# M3_Chip.net
KiCad netlist of a schematic drawn in Altium Designer
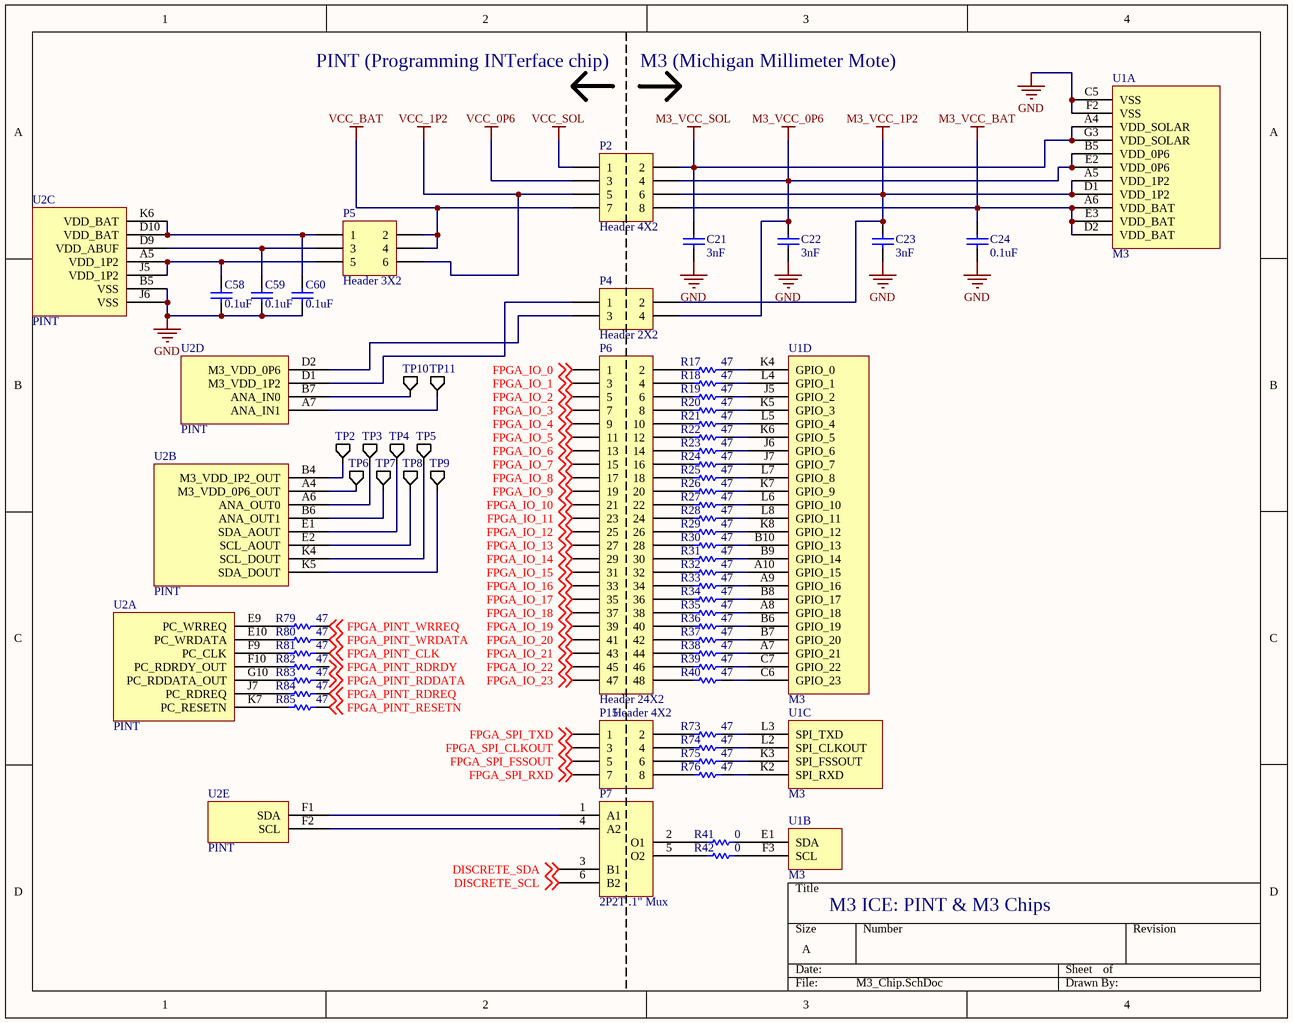
[diagram p0: M3_Chip.SchDoc]

(export (version "E")
  (design (tool "Eeschema 10.0.6"))
  (components
    (comp (ref "C21")
      (value "3nF")
      (footprint "1608[0603]")
      (description "Capacitor (Semiconductor SIM Model)")
      (fields
        (field (name "DISTPARTNO") "399-7893-1-ND")
        (field (name "MANPARTNO") "C0603C302K5GACTU")
        (field (name "PUBLISHER") "Altium Limited")
      )
      (libsource (lib "Miscellaneous Devices") (part "Cap Semi"))
    )
    (comp (ref "C22")
      (value "3nF")
      (footprint "1608[0603]")
      (description "Capacitor (Semiconductor SIM Model)")
      (fields
        (field (name "DISTPARTNO") "399-7893-1-ND")
        (field (name "MANPARTNO") "C0603C302K5GACTU")
        (field (name "PUBLISHER") "Altium Limited")
      )
      (libsource (lib "Miscellaneous Devices") (part "Cap Semi"))
    )
    (comp (ref "C23")
      (value "3nF")
      (footprint "1608[0603]")
      (description "Capacitor (Semiconductor SIM Model)")
      (fields
        (field (name "DISTPARTNO") "399-7893-1-ND")
        (field (name "MANPARTNO") "C0603C302K5GACTU")
        (field (name "PUBLISHER") "Altium Limited")
      )
      (libsource (lib "Miscellaneous Devices") (part "Cap Semi"))
    )
    (comp (ref "C24")
      (value "0.1uF")
      (footprint "1608[0603]")
      (description "Capacitor (Semiconductor SIM Model)")
      (fields
        (field (name "DISTPARTNO") "445-1317-1-ND")
        (field (name "MANPARTNO") "C1608X7R1C104K")
        (field (name "PUBLISHER") "Altium Limited")
      )
      (libsource (lib "Miscellaneous Devices") (part "Cap Semi"))
    )
    (comp (ref "C58")
      (value "0.1uF")
      (footprint "1608[0603]")
      (description "Capacitor (Semiconductor SIM Model)")
      (fields
        (field (name "DISTPARTNO") "445-1317-1-ND")
        (field (name "MANPARTNO") "C1608X7R1C104K")
        (field (name "PUBLISHER") "Altium Limited")
      )
      (libsource (lib "Miscellaneous Devices") (part "Cap Semi"))
    )
    (comp (ref "C59")
      (value "0.1uF")
      (footprint "1608[0603]")
      (description "Capacitor (Semiconductor SIM Model)")
      (fields
        (field (name "DISTPARTNO") "445-1317-1-ND")
        (field (name "MANPARTNO") "C1608X7R1C104K")
        (field (name "PUBLISHER") "Altium Limited")
      )
      (libsource (lib "Miscellaneous Devices") (part "Cap Semi"))
    )
    (comp (ref "C60")
      (value "0.1uF")
      (footprint "1608[0603]")
      (description "Capacitor (Semiconductor SIM Model)")
      (fields
        (field (name "DISTPARTNO") "445-1317-1-ND")
        (field (name "MANPARTNO") "C1608X7R1C104K")
        (field (name "PUBLISHER") "Altium Limited")
      )
      (libsource (lib "Miscellaneous Devices") (part "Cap Semi"))
    )
    (comp (ref "P2")
      (value "Header 4X2")
      (footprint "HDR2X4")
      (description "Header, 4-Pin, Dual row")
      (fields (field (name "PUBLISHER") "Altium Limited"))
      (libsource (lib "Miscellaneous Connectors") (part "Header 4X2"))
    )
    (comp (ref "P4")
      (value "Header 2X2")
      (footprint "HDR2X2")
      (description "Header, 2-Pin, Dual row")
      (fields (field (name "PUBLISHER") "Altium Limited"))
      (libsource (lib "Miscellaneous Connectors") (part "Header 2X2"))
    )
    (comp (ref "P5")
      (value "Header 3X2")
      (footprint "HDR2X3")
      (description "Header, 3-Pin, Dual row")
      (fields (field (name "PUBLISHER") "Altium Limited"))
      (libsource (lib "Miscellaneous Connectors") (part "Header 3X2"))
    )
    (comp (ref "P6")
      (value "Header 24X2")
      (footprint "HDR2X24")
      (description "Header, 24-Pin, Dual row")
      (fields (field (name "PUBLISHER") "Altium Limited"))
      (libsource (lib "Miscellaneous Connectors") (part "Header 24X2"))
    )
    (comp (ref "P7")
      (value "2P2T .1\" Mux")
      (footprint "HDR3x2")
      (libsource (lib "M3") (part "2P2T .1{dblquote} Mux"))
    )
    (comp (ref "P15")
      (value "Header 4X2")
      (footprint "HDR2X4")
      (description "Header, 4-Pin, Dual row")
      (fields (field (name "PUBLISHER") "Altium Limited"))
      (libsource (lib "Miscellaneous Connectors") (part "Header 4X2"))
    )
    (comp (ref "R17")
      (value "47")
      (footprint "0603")
      (description "Semiconductor Resistor")
      (fields
        (field (name "DISTPARTNO") "P47GCT-ND")
        (field (name "MANPARTNO") "ERJ-3GEYJ470V")
        (field (name "PUBLISHER") "Altium Limited")
      )
      (libsource (lib "M3") (part "Res Chip"))
    )
    (comp (ref "R18")
      (value "47")
      (footprint "0603")
      (description "Semiconductor Resistor")
      (fields
        (field (name "DISTPARTNO") "P47GCT-ND")
        (field (name "MANPARTNO") "ERJ-3GEYJ470V")
        (field (name "PUBLISHER") "Altium Limited")
      )
      (libsource (lib "M3") (part "Res Chip"))
    )
    (comp (ref "R19")
      (value "47")
      (footprint "0603")
      (description "Semiconductor Resistor")
      (fields
        (field (name "DISTPARTNO") "P47GCT-ND")
        (field (name "MANPARTNO") "ERJ-3GEYJ470V")
        (field (name "PUBLISHER") "Altium Limited")
      )
      (libsource (lib "M3") (part "Res Chip"))
    )
    (comp (ref "R20")
      (value "47")
      (footprint "0603")
      (description "Semiconductor Resistor")
      (fields
        (field (name "DISTPARTNO") "P47GCT-ND")
        (field (name "MANPARTNO") "ERJ-3GEYJ470V")
        (field (name "PUBLISHER") "Altium Limited")
      )
      (libsource (lib "M3") (part "Res Chip"))
    )
    (comp (ref "R21")
      (value "47")
      (footprint "0603")
      (description "Semiconductor Resistor")
      (fields
        (field (name "DISTPARTNO") "P47GCT-ND")
        (field (name "MANPARTNO") "ERJ-3GEYJ470V")
        (field (name "PUBLISHER") "Altium Limited")
      )
      (libsource (lib "M3") (part "Res Chip"))
    )
    (comp (ref "R22")
      (value "47")
      (footprint "0603")
      (description "Semiconductor Resistor")
      (fields
        (field (name "DISTPARTNO") "P47GCT-ND")
        (field (name "MANPARTNO") "ERJ-3GEYJ470V")
        (field (name "PUBLISHER") "Altium Limited")
      )
      (libsource (lib "M3") (part "Res Chip"))
    )
    (comp (ref "R23")
      (value "47")
      (footprint "0603")
      (description "Semiconductor Resistor")
      (fields
        (field (name "DISTPARTNO") "P47GCT-ND")
        (field (name "MANPARTNO") "ERJ-3GEYJ470V")
        (field (name "PUBLISHER") "Altium Limited")
      )
      (libsource (lib "M3") (part "Res Chip"))
    )
    (comp (ref "R24")
      (value "47")
      (footprint "0603")
      (description "Semiconductor Resistor")
      (fields
        (field (name "DISTPARTNO") "P47GCT-ND")
        (field (name "MANPARTNO") "ERJ-3GEYJ470V")
        (field (name "PUBLISHER") "Altium Limited")
      )
      (libsource (lib "M3") (part "Res Chip"))
    )
    (comp (ref "R25")
      (value "47")
      (footprint "0603")
      (description "Semiconductor Resistor")
      (fields
        (field (name "DISTPARTNO") "P47GCT-ND")
        (field (name "MANPARTNO") "ERJ-3GEYJ470V")
        (field (name "PUBLISHER") "Altium Limited")
      )
      (libsource (lib "M3") (part "Res Chip"))
    )
    (comp (ref "R26")
      (value "47")
      (footprint "0603")
      (description "Semiconductor Resistor")
      (fields
        (field (name "DISTPARTNO") "P47GCT-ND")
        (field (name "MANPARTNO") "ERJ-3GEYJ470V")
        (field (name "PUBLISHER") "Altium Limited")
      )
      (libsource (lib "M3") (part "Res Chip"))
    )
    (comp (ref "R27")
      (value "47")
      (footprint "0603")
      (description "Semiconductor Resistor")
      (fields
        (field (name "DISTPARTNO") "P47GCT-ND")
        (field (name "MANPARTNO") "ERJ-3GEYJ470V")
        (field (name "PUBLISHER") "Altium Limited")
      )
      (libsource (lib "M3") (part "Res Chip"))
    )
    (comp (ref "R28")
      (value "47")
      (footprint "0603")
      (description "Semiconductor Resistor")
      (fields
        (field (name "DISTPARTNO") "P47GCT-ND")
        (field (name "MANPARTNO") "ERJ-3GEYJ470V")
        (field (name "PUBLISHER") "Altium Limited")
      )
      (libsource (lib "M3") (part "Res Chip"))
    )
    (comp (ref "R29")
      (value "47")
      (footprint "0603")
      (description "Semiconductor Resistor")
      (fields
        (field (name "DISTPARTNO") "P47GCT-ND")
        (field (name "MANPARTNO") "ERJ-3GEYJ470V")
        (field (name "PUBLISHER") "Altium Limited")
      )
      (libsource (lib "M3") (part "Res Chip"))
    )
    (comp (ref "R30")
      (value "47")
      (footprint "0603")
      (description "Semiconductor Resistor")
      (fields
        (field (name "DISTPARTNO") "P47GCT-ND")
        (field (name "MANPARTNO") "ERJ-3GEYJ470V")
        (field (name "PUBLISHER") "Altium Limited")
      )
      (libsource (lib "M3") (part "Res Chip"))
    )
    (comp (ref "R31")
      (value "47")
      (footprint "0603")
      (description "Semiconductor Resistor")
      (fields
        (field (name "DISTPARTNO") "P47GCT-ND")
        (field (name "MANPARTNO") "ERJ-3GEYJ470V")
        (field (name "PUBLISHER") "Altium Limited")
      )
      (libsource (lib "M3") (part "Res Chip"))
    )
    (comp (ref "R32")
      (value "47")
      (footprint "0603")
      (description "Semiconductor Resistor")
      (fields
        (field (name "DISTPARTNO") "P47GCT-ND")
        (field (name "MANPARTNO") "ERJ-3GEYJ470V")
        (field (name "PUBLISHER") "Altium Limited")
      )
      (libsource (lib "M3") (part "Res Chip"))
    )
    (comp (ref "R33")
      (value "47")
      (footprint "0603")
      (description "Semiconductor Resistor")
      (fields
        (field (name "DISTPARTNO") "P47GCT-ND")
        (field (name "MANPARTNO") "ERJ-3GEYJ470V")
        (field (name "PUBLISHER") "Altium Limited")
      )
      (libsource (lib "M3") (part "Res Chip"))
    )
    (comp (ref "R34")
      (value "47")
      (footprint "0603")
      (description "Semiconductor Resistor")
      (fields
        (field (name "DISTPARTNO") "P47GCT-ND")
        (field (name "MANPARTNO") "ERJ-3GEYJ470V")
        (field (name "PUBLISHER") "Altium Limited")
      )
      (libsource (lib "M3") (part "Res Chip"))
    )
    (comp (ref "R35")
      (value "47")
      (footprint "0603")
      (description "Semiconductor Resistor")
      (fields
        (field (name "DISTPARTNO") "P47GCT-ND")
        (field (name "MANPARTNO") "ERJ-3GEYJ470V")
        (field (name "PUBLISHER") "Altium Limited")
      )
      (libsource (lib "M3") (part "Res Chip"))
    )
    (comp (ref "R36")
      (value "47")
      (footprint "0603")
      (description "Semiconductor Resistor")
      (fields
        (field (name "DISTPARTNO") "P47GCT-ND")
        (field (name "MANPARTNO") "ERJ-3GEYJ470V")
        (field (name "PUBLISHER") "Altium Limited")
      )
      (libsource (lib "M3") (part "Res Chip"))
    )
    (comp (ref "R37")
      (value "47")
      (footprint "0603")
      (description "Semiconductor Resistor")
      (fields
        (field (name "DISTPARTNO") "P47GCT-ND")
        (field (name "MANPARTNO") "ERJ-3GEYJ470V")
        (field (name "PUBLISHER") "Altium Limited")
      )
      (libsource (lib "M3") (part "Res Chip"))
    )
    (comp (ref "R38")
      (value "47")
      (footprint "0603")
      (description "Semiconductor Resistor")
      (fields
        (field (name "DISTPARTNO") "P47GCT-ND")
        (field (name "MANPARTNO") "ERJ-3GEYJ470V")
        (field (name "PUBLISHER") "Altium Limited")
      )
      (libsource (lib "M3") (part "Res Chip"))
    )
    (comp (ref "R39")
      (value "47")
      (footprint "0603")
      (description "Semiconductor Resistor")
      (fields
        (field (name "DISTPARTNO") "P47GCT-ND")
        (field (name "MANPARTNO") "ERJ-3GEYJ470V")
        (field (name "PUBLISHER") "Altium Limited")
      )
      (libsource (lib "M3") (part "Res Chip"))
    )
    (comp (ref "R40")
      (value "47")
      (footprint "0603")
      (description "Semiconductor Resistor")
      (fields
        (field (name "DISTPARTNO") "P47GCT-ND")
        (field (name "MANPARTNO") "ERJ-3GEYJ470V")
        (field (name "PUBLISHER") "Altium Limited")
      )
      (libsource (lib "M3") (part "Res Chip"))
    )
    (comp (ref "R41")
      (value "0")
      (footprint "0603")
      (description "Semiconductor Resistor")
      (fields
        (field (name "DISTPARTNO") "P0.0GCT-ND")
        (field (name "MANPARTNO") "ERJ-3GEY0R00V")
        (field (name "PUBLISHER") "Altium Limited")
      )
      (libsource (lib "M3") (part "Res Chip"))
    )
    (comp (ref "R42")
      (value "0")
      (footprint "0603")
      (description "Semiconductor Resistor")
      (fields
        (field (name "DISTPARTNO") "P0.0GCT-ND")
        (field (name "MANPARTNO") "ERJ-3GEY0R00V")
        (field (name "PUBLISHER") "Altium Limited")
      )
      (libsource (lib "M3") (part "Res Chip"))
    )
    (comp (ref "R73")
      (value "47")
      (footprint "0603")
      (description "Semiconductor Resistor")
      (fields
        (field (name "DISTPARTNO") "P47GCT-ND")
        (field (name "MANPARTNO") "ERJ-3GEYJ470V")
        (field (name "PUBLISHER") "Altium Limited")
      )
      (libsource (lib "M3") (part "Res Chip"))
    )
    (comp (ref "R74")
      (value "47")
      (footprint "0603")
      (description "Semiconductor Resistor")
      (fields
        (field (name "DISTPARTNO") "P47GCT-ND")
        (field (name "MANPARTNO") "ERJ-3GEYJ470V")
        (field (name "PUBLISHER") "Altium Limited")
      )
      (libsource (lib "M3") (part "Res Chip"))
    )
    (comp (ref "R75")
      (value "47")
      (footprint "0603")
      (description "Semiconductor Resistor")
      (fields
        (field (name "DISTPARTNO") "P47GCT-ND")
        (field (name "MANPARTNO") "ERJ-3GEYJ470V")
        (field (name "PUBLISHER") "Altium Limited")
      )
      (libsource (lib "M3") (part "Res Chip"))
    )
    (comp (ref "R76")
      (value "47")
      (footprint "0603")
      (description "Semiconductor Resistor")
      (fields
        (field (name "DISTPARTNO") "P47GCT-ND")
        (field (name "MANPARTNO") "ERJ-3GEYJ470V")
        (field (name "PUBLISHER") "Altium Limited")
      )
      (libsource (lib "M3") (part "Res Chip"))
    )
    (comp (ref "R79")
      (value "47")
      (footprint "0603")
      (description "Semiconductor Resistor")
      (fields
        (field (name "DISTPARTNO") "P47GCT-ND")
        (field (name "MANPARTNO") "ERJ-3GEYJ470V")
        (field (name "PUBLISHER") "Altium Limited")
      )
      (libsource (lib "M3") (part "Res Chip"))
    )
    (comp (ref "R80")
      (value "47")
      (footprint "0603")
      (description "Semiconductor Resistor")
      (fields
        (field (name "DISTPARTNO") "P47GCT-ND")
        (field (name "MANPARTNO") "ERJ-3GEYJ470V")
        (field (name "PUBLISHER") "Altium Limited")
      )
      (libsource (lib "M3") (part "Res Chip"))
    )
    (comp (ref "R81")
      (value "47")
      (footprint "0603")
      (description "Semiconductor Resistor")
      (fields
        (field (name "DISTPARTNO") "P47GCT-ND")
        (field (name "MANPARTNO") "ERJ-3GEYJ470V")
        (field (name "PUBLISHER") "Altium Limited")
      )
      (libsource (lib "M3") (part "Res Chip"))
    )
    (comp (ref "R82")
      (value "47")
      (footprint "0603")
      (description "Semiconductor Resistor")
      (fields
        (field (name "DISTPARTNO") "P47GCT-ND")
        (field (name "MANPARTNO") "ERJ-3GEYJ470V")
        (field (name "PUBLISHER") "Altium Limited")
      )
      (libsource (lib "M3") (part "Res Chip"))
    )
    (comp (ref "R83")
      (value "47")
      (footprint "0603")
      (description "Semiconductor Resistor")
      (fields
        (field (name "DISTPARTNO") "P47GCT-ND")
        (field (name "MANPARTNO") "ERJ-3GEYJ470V")
        (field (name "PUBLISHER") "Altium Limited")
      )
      (libsource (lib "M3") (part "Res Chip"))
    )
    (comp (ref "R84")
      (value "47")
      (footprint "0603")
      (description "Semiconductor Resistor")
      (fields
        (field (name "DISTPARTNO") "P47GCT-ND")
        (field (name "MANPARTNO") "ERJ-3GEYJ470V")
        (field (name "PUBLISHER") "Altium Limited")
      )
      (libsource (lib "M3") (part "Res Chip"))
    )
    (comp (ref "R85")
      (value "47")
      (footprint "0603")
      (description "Semiconductor Resistor")
      (fields
        (field (name "DISTPARTNO") "P47GCT-ND")
        (field (name "MANPARTNO") "ERJ-3GEYJ470V")
        (field (name "PUBLISHER") "Altium Limited")
      )
      (libsource (lib "M3") (part "Res Chip"))
    )
    (comp (ref "TP2") (value "TP") (footprint "TP") (libsource (lib "M3") (part "TP")))
    (comp (ref "TP3") (value "TP") (footprint "TP") (libsource (lib "M3") (part "TP")))
    (comp (ref "TP4") (value "TP") (footprint "TP") (libsource (lib "M3") (part "TP")))
    (comp (ref "TP5") (value "TP") (footprint "TP") (libsource (lib "M3") (part "TP")))
    (comp (ref "TP6") (value "TP") (footprint "TP") (libsource (lib "M3") (part "TP")))
    (comp (ref "TP7") (value "TP") (footprint "TP") (libsource (lib "M3") (part "TP")))
    (comp (ref "TP8") (value "TP") (footprint "TP") (libsource (lib "M3") (part "TP")))
    (comp (ref "TP9") (value "TP") (footprint "TP") (libsource (lib "M3") (part "TP")))
    (comp (ref "TP10") (value "TP") (footprint "TP") (libsource (lib "M3") (part "TP")))
    (comp (ref "TP11") (value "TP") (footprint "TP") (libsource (lib "M3") (part "TP")))
    (comp (ref "U1")
      (value "M3")
      (footprint "CPGA-84")
      (fields (field (name "DISTPARTNO") "3M5067-ND") (field (name "MANPARTNO") "200-6311-9UN-1900"))
      (libsource (lib "M3") (part "M3"))
    )
    (comp (ref "U2")
      (value "PINT")
      (footprint "CPGA-65")
      (fields (field (name "DISTPARTNO") "3M5066-ND") (field (name "MANPARTNO") "200-6310-9UN-1900"))
      (libsource (lib "M3") (part "PINT"))
    )
  )
  (nets
    (net (code "1") (name "DISCRETE_SCL") (class "Default")
      (node (ref "P7") (pin "6") (pinfunction "B2_6") (pintype "passive"))
    )
    (net (code "2") (name "DISCRETE_SDA") (class "Default")
      (node (ref "P7") (pin "3") (pinfunction "B1_3") (pintype "passive"))
    )
    (net (code "3") (name "FPGA_IO_0") (class "Default")
      (node (ref "P6") (pin "1") (pinfunction "1_1") (pintype "passive"))
    )
    (net (code "4") (name "FPGA_IO_1") (class "Default")
      (node (ref "P6") (pin "3") (pinfunction "3_3") (pintype "passive"))
    )
    (net (code "5") (name "FPGA_IO_2") (class "Default")
      (node (ref "P6") (pin "5") (pinfunction "5_5") (pintype "passive"))
    )
    (net (code "6") (name "FPGA_IO_3") (class "Default")
      (node (ref "P6") (pin "7") (pinfunction "7_7") (pintype "passive"))
    )
    (net (code "7") (name "FPGA_IO_4") (class "Default")
      (node (ref "P6") (pin "9") (pinfunction "9_9") (pintype "passive"))
    )
    (net (code "8") (name "FPGA_IO_5") (class "Default")
      (node (ref "P6") (pin "11") (pinfunction "11_11") (pintype "passive"))
    )
    (net (code "9") (name "FPGA_IO_6") (class "Default")
      (node (ref "P6") (pin "13") (pinfunction "13_13") (pintype "passive"))
    )
    (net (code "10") (name "FPGA_IO_7") (class "Default")
      (node (ref "P6") (pin "15") (pinfunction "15_15") (pintype "passive"))
    )
    (net (code "11") (name "FPGA_IO_8") (class "Default")
      (node (ref "P6") (pin "17") (pinfunction "17_17") (pintype "passive"))
    )
    (net (code "12") (name "FPGA_IO_9") (class "Default")
      (node (ref "P6") (pin "19") (pinfunction "19_19") (pintype "passive"))
    )
    (net (code "13") (name "FPGA_IO_10") (class "Default")
      (node (ref "P6") (pin "21") (pinfunction "21_21") (pintype "passive"))
    )
    (net (code "14") (name "FPGA_IO_11") (class "Default")
      (node (ref "P6") (pin "23") (pinfunction "23_23") (pintype "passive"))
    )
    (net (code "15") (name "FPGA_IO_12") (class "Default")
      (node (ref "P6") (pin "25") (pinfunction "25_25") (pintype "passive"))
    )
    (net (code "16") (name "FPGA_IO_13") (class "Default")
      (node (ref "P6") (pin "27") (pinfunction "27_27") (pintype "passive"))
    )
    (net (code "17") (name "FPGA_IO_14") (class "Default")
      (node (ref "P6") (pin "29") (pinfunction "29_29") (pintype "passive"))
    )
    (net (code "18") (name "FPGA_IO_15") (class "Default")
      (node (ref "P6") (pin "31") (pinfunction "31_31") (pintype "passive"))
    )
    (net (code "19") (name "FPGA_IO_16") (class "Default")
      (node (ref "P6") (pin "33") (pinfunction "33_33") (pintype "passive"))
    )
    (net (code "20") (name "FPGA_IO_17") (class "Default")
      (node (ref "P6") (pin "35") (pinfunction "35_35") (pintype "passive"))
    )
    (net (code "21") (name "FPGA_IO_18") (class "Default")
      (node (ref "P6") (pin "37") (pinfunction "37_37") (pintype "passive"))
    )
    (net (code "22") (name "FPGA_IO_19") (class "Default")
      (node (ref "P6") (pin "39") (pinfunction "39_39") (pintype "passive"))
    )
    (net (code "23") (name "FPGA_IO_20") (class "Default")
      (node (ref "P6") (pin "41") (pinfunction "41_41") (pintype "passive"))
    )
    (net (code "24") (name "FPGA_IO_21") (class "Default")
      (node (ref "P6") (pin "43") (pinfunction "43_43") (pintype "passive"))
    )
    (net (code "25") (name "FPGA_IO_22") (class "Default")
      (node (ref "P6") (pin "45") (pinfunction "45_45") (pintype "passive"))
    )
    (net (code "26") (name "FPGA_IO_23") (class "Default")
      (node (ref "P6") (pin "47") (pinfunction "47_47") (pintype "passive"))
    )
    (net (code "27") (name "FPGA_PINT_CLK") (class "Default")
      (node (ref "R81") (pin "1") (pinfunction "1_1") (pintype "passive"))
    )
    (net (code "28") (name "FPGA_PINT_RDDATA") (class "Default")
      (node (ref "R83") (pin "1") (pinfunction "1_1") (pintype "passive"))
    )
    (net (code "29") (name "FPGA_PINT_RDRDY") (class "Default")
      (node (ref "R82") (pin "1") (pinfunction "1_1") (pintype "passive"))
    )
    (net (code "30") (name "FPGA_PINT_RDREQ") (class "Default")
      (node (ref "R84") (pin "1") (pinfunction "1_1") (pintype "passive"))
    )
    (net (code "31") (name "FPGA_PINT_RESETN") (class "Default")
      (node (ref "R85") (pin "1") (pinfunction "1_1") (pintype "passive"))
    )
    (net (code "32") (name "FPGA_PINT_WRDATA") (class "Default")
      (node (ref "R80") (pin "1") (pinfunction "1_1") (pintype "passive"))
    )
    (net (code "33") (name "FPGA_PINT_WRREQ") (class "Default")
      (node (ref "R79") (pin "1") (pinfunction "1_1") (pintype "passive"))
    )
    (net (code "34") (name "FPGA_SPI_CLKOUT") (class "Default")
      (node (ref "P15") (pin "3") (pinfunction "3_3") (pintype "passive"))
    )
    (net (code "35") (name "FPGA_SPI_FSSOUT") (class "Default")
      (node (ref "P15") (pin "5") (pinfunction "5_5") (pintype "passive"))
    )
    (net (code "36") (name "FPGA_SPI_RXD") (class "Default")
      (node (ref "P15") (pin "7") (pinfunction "7_7") (pintype "passive"))
    )
    (net (code "37") (name "FPGA_SPI_TXD") (class "Default")
      (node (ref "P15") (pin "1") (pinfunction "1_1") (pintype "passive"))
    )
    (net (code "38") (name "GND") (class "Default")
      (node (ref "C21") (pin "1") (pinfunction "1_1") (pintype "passive"))
      (node (ref "C22") (pin "1") (pinfunction "1_1") (pintype "passive"))
      (node (ref "C23") (pin "1") (pinfunction "1_1") (pintype "passive"))
      (node (ref "C24") (pin "1") (pinfunction "1_1") (pintype "passive"))
      (node (ref "C58") (pin "1") (pinfunction "1_1") (pintype "passive"))
      (node (ref "C59") (pin "1") (pinfunction "1_1") (pintype "passive"))
      (node (ref "C60") (pin "1") (pinfunction "1_1") (pintype "passive"))
      (node (ref "U1") (pin "C5") (pinfunction "VSS_C5") (pintype "passive"))
      (node (ref "U1") (pin "F2") (pinfunction "VSS_F2") (pintype "passive"))
      (node (ref "U2") (pin "B5") (pinfunction "VSS_B5") (pintype "passive"))
      (node (ref "U2") (pin "J6") (pinfunction "VSS_J6") (pintype "passive"))
    )
    (net (code "39") (name "M3_VCC_0P6") (class "Default")
      (node (ref "C22") (pin "2") (pinfunction "2_2") (pintype "passive"))
      (node (ref "P2") (pin "4") (pinfunction "4_4") (pintype "passive"))
      (node (ref "P4") (pin "4") (pinfunction "4_4") (pintype "passive"))
      (node (ref "U1") (pin "B5") (pinfunction "VDD_0P6_B5") (pintype "passive"))
      (node (ref "U1") (pin "E2") (pinfunction "VDD_0P6_E2") (pintype "passive"))
    )
    (net (code "40") (name "M3_VCC_1P2") (class "Default")
      (node (ref "C23") (pin "2") (pinfunction "2_2") (pintype "passive"))
      (node (ref "P2") (pin "6") (pinfunction "6_6") (pintype "passive"))
      (node (ref "P4") (pin "2") (pinfunction "2_2") (pintype "passive"))
      (node (ref "U1") (pin "A5") (pinfunction "VDD_1P2_A5") (pintype "passive"))
      (node (ref "U1") (pin "D1") (pinfunction "VDD_1P2_D1") (pintype "passive"))
    )
    (net (code "41") (name "M3_VCC_BAT") (class "Default")
      (node (ref "C24") (pin "2") (pinfunction "2_2") (pintype "passive"))
      (node (ref "P2") (pin "8") (pinfunction "8_8") (pintype "passive"))
      (node (ref "U1") (pin "A6") (pinfunction "VDD_BAT_A6") (pintype "passive"))
      (node (ref "U1") (pin "D2") (pinfunction "VDD_BAT_D2") (pintype "passive"))
      (node (ref "U1") (pin "E3") (pinfunction "VDD_BAT_E3") (pintype "passive"))
    )
    (net (code "42") (name "M3_VCC_SOL") (class "Default")
      (node (ref "C21") (pin "2") (pinfunction "2_2") (pintype "passive"))
      (node (ref "P2") (pin "2") (pinfunction "2_2") (pintype "passive"))
      (node (ref "U1") (pin "A4") (pinfunction "VDD_SOLAR_A4") (pintype "passive"))
      (node (ref "U1") (pin "G3") (pinfunction "VDD_SOLAR_G3") (pintype "passive"))
    )
    (net (code "43") (name "Net-(C58-Pad2)") (class "Default")
      (node (ref "C58") (pin "2") (pinfunction "2_2") (pintype "passive"))
      (node (ref "P5") (pin "5") (pinfunction "5_5") (pintype "passive"))
      (node (ref "U2") (pin "A5") (pinfunction "VDD_1P2_A5") (pintype "passive"))
      (node (ref "U2") (pin "J5") (pinfunction "VDD_1P2_J5") (pintype "passive"))
    )
    (net (code "44") (name "Net-(C60-Pad2)") (class "Default")
      (node (ref "C60") (pin "2") (pinfunction "2_2") (pintype "passive"))
      (node (ref "P5") (pin "1") (pinfunction "1_1") (pintype "passive"))
      (node (ref "U2") (pin "D10") (pinfunction "VDD_BAT_D10") (pintype "passive"))
      (node (ref "U2") (pin "K6") (pinfunction "VDD_BAT_K6") (pintype "passive"))
    )
    (net (code "45") (name "Net-(P6-Pad2)") (class "Default")
      (node (ref "P6") (pin "2") (pinfunction "2_2") (pintype "passive"))
      (node (ref "R17") (pin "2") (pinfunction "2_2") (pintype "passive"))
    )
    (net (code "46") (name "Net-(P6-Pad4)") (class "Default")
      (node (ref "P6") (pin "4") (pinfunction "4_4") (pintype "passive"))
      (node (ref "R18") (pin "2") (pinfunction "2_2") (pintype "passive"))
    )
    (net (code "47") (name "Net-(P6-Pad6)") (class "Default")
      (node (ref "P6") (pin "6") (pinfunction "6_6") (pintype "passive"))
      (node (ref "R19") (pin "2") (pinfunction "2_2") (pintype "passive"))
    )
    (net (code "48") (name "Net-(P6-Pad8)") (class "Default")
      (node (ref "P6") (pin "8") (pinfunction "8_8") (pintype "passive"))
      (node (ref "R20") (pin "2") (pinfunction "2_2") (pintype "passive"))
    )
    (net (code "49") (name "Net-(P6-Pad10)") (class "Default")
      (node (ref "P6") (pin "10") (pinfunction "10_10") (pintype "passive"))
      (node (ref "R21") (pin "2") (pinfunction "2_2") (pintype "passive"))
    )
    (net (code "50") (name "Net-(P6-Pad12)") (class "Default")
      (node (ref "P6") (pin "12") (pinfunction "12_12") (pintype "passive"))
      (node (ref "R22") (pin "2") (pinfunction "2_2") (pintype "passive"))
    )
    (net (code "51") (name "Net-(P6-Pad14)") (class "Default")
      (node (ref "P6") (pin "14") (pinfunction "14_14") (pintype "passive"))
      (node (ref "R23") (pin "2") (pinfunction "2_2") (pintype "passive"))
    )
    (net (code "52") (name "Net-(P6-Pad16)") (class "Default")
      (node (ref "P6") (pin "16") (pinfunction "16_16") (pintype "passive"))
      (node (ref "R24") (pin "2") (pinfunction "2_2") (pintype "passive"))
    )
    (net (code "53") (name "Net-(P6-Pad18)") (class "Default")
      (node (ref "P6") (pin "18") (pinfunction "18_18") (pintype "passive"))
      (node (ref "R25") (pin "2") (pinfunction "2_2") (pintype "passive"))
    )
    (net (code "54") (name "Net-(P6-Pad20)") (class "Default")
      (node (ref "P6") (pin "20") (pinfunction "20_20") (pintype "passive"))
      (node (ref "R26") (pin "2") (pinfunction "2_2") (pintype "passive"))
    )
    (net (code "55") (name "Net-(P6-Pad22)") (class "Default")
      (node (ref "P6") (pin "22") (pinfunction "22_22") (pintype "passive"))
      (node (ref "R27") (pin "2") (pinfunction "2_2") (pintype "passive"))
    )
    (net (code "56") (name "Net-(P6-Pad24)") (class "Default")
      (node (ref "P6") (pin "24") (pinfunction "24_24") (pintype "passive"))
      (node (ref "R28") (pin "2") (pinfunction "2_2") (pintype "passive"))
    )
    (net (code "57") (name "Net-(P6-Pad26)") (class "Default")
      (node (ref "P6") (pin "26") (pinfunction "26_26") (pintype "passive"))
      (node (ref "R29") (pin "2") (pinfunction "2_2") (pintype "passive"))
    )
    (net (code "58") (name "Net-(P6-Pad28)") (class "Default")
      (node (ref "P6") (pin "28") (pinfunction "28_28") (pintype "passive"))
      (node (ref "R30") (pin "2") (pinfunction "2_2") (pintype "passive"))
    )
    (net (code "59") (name "Net-(P6-Pad30)") (class "Default")
      (node (ref "P6") (pin "30") (pinfunction "30_30") (pintype "passive"))
      (node (ref "R31") (pin "2") (pinfunction "2_2") (pintype "passive"))
    )
    (net (code "60") (name "Net-(P6-Pad32)") (class "Default")
      (node (ref "P6") (pin "32") (pinfunction "32_32") (pintype "passive"))
      (node (ref "R32") (pin "2") (pinfunction "2_2") (pintype "passive"))
    )
    (net (code "61") (name "Net-(P6-Pad34)") (class "Default")
      (node (ref "P6") (pin "34") (pinfunction "34_34") (pintype "passive"))
      (node (ref "R33") (pin "2") (pinfunction "2_2") (pintype "passive"))
    )
    (net (code "62") (name "Net-(P6-Pad36)") (class "Default")
      (node (ref "P6") (pin "36") (pinfunction "36_36") (pintype "passive"))
      (node (ref "R34") (pin "2") (pinfunction "2_2") (pintype "passive"))
    )
    (net (code "63") (name "Net-(P6-Pad38)") (class "Default")
      (node (ref "P6") (pin "38") (pinfunction "38_38") (pintype "passive"))
      (node (ref "R35") (pin "2") (pinfunction "2_2") (pintype "passive"))
    )
    (net (code "64") (name "Net-(P6-Pad40)") (class "Default")
      (node (ref "P6") (pin "40") (pinfunction "40_40") (pintype "passive"))
      (node (ref "R36") (pin "2") (pinfunction "2_2") (pintype "passive"))
    )
    (net (code "65") (name "Net-(P6-Pad42)") (class "Default")
      (node (ref "P6") (pin "42") (pinfunction "42_42") (pintype "passive"))
      (node (ref "R37") (pin "2") (pinfunction "2_2") (pintype "passive"))
    )
    (net (code "66") (name "Net-(P6-Pad44)") (class "Default")
      (node (ref "P6") (pin "44") (pinfunction "44_44") (pintype "passive"))
      (node (ref "R38") (pin "2") (pinfunction "2_2") (pintype "passive"))
    )
    (net (code "67") (name "Net-(P6-Pad46)") (class "Default")
      (node (ref "P6") (pin "46") (pinfunction "46_46") (pintype "passive"))
      (node (ref "R39") (pin "2") (pinfunction "2_2") (pintype "passive"))
    )
    (net (code "68") (name "Net-(P6-Pad48)") (class "Default")
      (node (ref "P6") (pin "48") (pinfunction "48_48") (pintype "passive"))
      (node (ref "R40") (pin "2") (pinfunction "2_2") (pintype "passive"))
    )
    (net (code "69") (name "Net-(P7-A1)") (class "Default")
      (node (ref "P7") (pin "1") (pinfunction "A1_1") (pintype "passive"))
      (node (ref "U2") (pin "F1") (pinfunction "SDA_F1") (pintype "passive"))
    )
    (net (code "70") (name "Net-(P7-A2)") (class "Default")
      (node (ref "P7") (pin "4") (pinfunction "A2_4") (pintype "passive"))
      (node (ref "U2") (pin "F2") (pinfunction "SCL_F2") (pintype "passive"))
    )
    (net (code "71") (name "Net-(P7-O1)") (class "Default")
      (node (ref "P7") (pin "2") (pinfunction "O1_2") (pintype "passive"))
      (node (ref "R41") (pin "2") (pinfunction "2_2") (pintype "passive"))
    )
    (net (code "72") (name "Net-(P7-O2)") (class "Default")
      (node (ref "P7") (pin "5") (pinfunction "O2_5") (pintype "passive"))
      (node (ref "R42") (pin "2") (pinfunction "2_2") (pintype "passive"))
    )
    (net (code "73") (name "Net-(P15-Pad2)") (class "Default")
      (node (ref "P15") (pin "2") (pinfunction "2_2") (pintype "passive"))
      (node (ref "R73") (pin "2") (pinfunction "2_2") (pintype "passive"))
    )
    (net (code "74") (name "Net-(P15-Pad4)") (class "Default")
      (node (ref "P15") (pin "4") (pinfunction "4_4") (pintype "passive"))
      (node (ref "R74") (pin "2") (pinfunction "2_2") (pintype "passive"))
    )
    (net (code "75") (name "Net-(P15-Pad6)") (class "Default")
      (node (ref "P15") (pin "6") (pinfunction "6_6") (pintype "passive"))
      (node (ref "R75") (pin "2") (pinfunction "2_2") (pintype "passive"))
    )
    (net (code "76") (name "Net-(P15-Pad8)") (class "Default")
      (node (ref "P15") (pin "8") (pinfunction "8_8") (pintype "passive"))
      (node (ref "R76") (pin "2") (pinfunction "2_2") (pintype "passive"))
    )
    (net (code "77") (name "Net-(TP2-A)") (class "Default")
      (node (ref "TP2") (pin "1") (pinfunction "A_1") (pintype "passive"))
      (node (ref "U2") (pin "B4") (pinfunction "M3_VDD_IP2_OUT_B4") (pintype "passive"))
    )
    (net (code "78") (name "Net-(TP3-A)") (class "Default")
      (node (ref "TP3") (pin "1") (pinfunction "A_1") (pintype "passive"))
      (node (ref "U2") (pin "A6") (pinfunction "ANA_OUT0_A6") (pintype "passive"))
    )
    (net (code "79") (name "Net-(TP4-A)") (class "Default")
      (node (ref "TP4") (pin "1") (pinfunction "A_1") (pintype "passive"))
      (node (ref "U2") (pin "E1") (pinfunction "SDA_AOUT_E1") (pintype "passive"))
    )
    (net (code "80") (name "Net-(TP5-A)") (class "Default")
      (node (ref "TP5") (pin "1") (pinfunction "A_1") (pintype "passive"))
      (node (ref "U2") (pin "K4") (pinfunction "SCL_DOUT_K4") (pintype "passive"))
    )
    (net (code "81") (name "Net-(TP6-A)") (class "Default")
      (node (ref "TP6") (pin "1") (pinfunction "A_1") (pintype "passive"))
      (node (ref "U2") (pin "A4") (pinfunction "M3_VDD_0P6_OUT_A4") (pintype "passive"))
    )
    (net (code "82") (name "Net-(TP7-A)") (class "Default")
      (node (ref "TP7") (pin "1") (pinfunction "A_1") (pintype "passive"))
      (node (ref "U2") (pin "B6") (pinfunction "ANA_OUT1_B6") (pintype "passive"))
    )
    (net (code "83") (name "Net-(TP8-A)") (class "Default")
      (node (ref "TP8") (pin "1") (pinfunction "A_1") (pintype "passive"))
      (node (ref "U2") (pin "E2") (pinfunction "SCL_AOUT_E2") (pintype "passive"))
    )
    (net (code "84") (name "Net-(TP9-A)") (class "Default")
      (node (ref "TP9") (pin "1") (pinfunction "A_1") (pintype "passive"))
      (node (ref "U2") (pin "K5") (pinfunction "SDA_DOUT_K5") (pintype "passive"))
    )
    (net (code "85") (name "Net-(TP10-A)") (class "Default")
      (node (ref "TP10") (pin "1") (pinfunction "A_1") (pintype "passive"))
      (node (ref "U2") (pin "B7") (pinfunction "ANA_IN0_B7") (pintype "passive"))
    )
    (net (code "86") (name "Net-(TP11-A)") (class "Default")
      (node (ref "TP11") (pin "1") (pinfunction "A_1") (pintype "passive"))
      (node (ref "U2") (pin "A7") (pinfunction "ANA_IN1_A7") (pintype "passive"))
    )
    (net (code "87") (name "Net-(U1B-SCL)") (class "Default")
      (node (ref "R42") (pin "1") (pinfunction "1_1") (pintype "passive"))
      (node (ref "U1") (pin "F3") (pinfunction "SCL_F3") (pintype "passive"))
    )
    (net (code "88") (name "Net-(U1B-SDA)") (class "Default")
      (node (ref "R41") (pin "1") (pinfunction "1_1") (pintype "passive"))
      (node (ref "U1") (pin "E1") (pinfunction "SDA_E1") (pintype "passive"))
    )
    (net (code "89") (name "Net-(U1C-SPI_CLKOUT)") (class "Default")
      (node (ref "R74") (pin "1") (pinfunction "1_1") (pintype "passive"))
      (node (ref "U1") (pin "L2") (pinfunction "SPI_CLKOUT_L2") (pintype "passive"))
    )
    (net (code "90") (name "Net-(U1C-SPI_FSSOUT)") (class "Default")
      (node (ref "R75") (pin "1") (pinfunction "1_1") (pintype "passive"))
      (node (ref "U1") (pin "K3") (pinfunction "SPI_FSSOUT_K3") (pintype "passive"))
    )
    (net (code "91") (name "Net-(U1C-SPI_RXD)") (class "Default")
      (node (ref "R76") (pin "1") (pinfunction "1_1") (pintype "passive"))
      (node (ref "U1") (pin "K2") (pinfunction "SPI_RXD_K2") (pintype "passive"))
    )
    (net (code "92") (name "Net-(U1C-SPI_TXD)") (class "Default")
      (node (ref "R73") (pin "1") (pinfunction "1_1") (pintype "passive"))
      (node (ref "U1") (pin "L3") (pinfunction "SPI_TXD_L3") (pintype "passive"))
    )
    (net (code "93") (name "Net-(U1D-GPIO_0)") (class "Default")
      (node (ref "R17") (pin "1") (pinfunction "1_1") (pintype "passive"))
      (node (ref "U1") (pin "K4") (pinfunction "GPIO_0_K4") (pintype "passive"))
    )
    (net (code "94") (name "Net-(U1D-GPIO_1)") (class "Default")
      (node (ref "R18") (pin "1") (pinfunction "1_1") (pintype "passive"))
      (node (ref "U1") (pin "L4") (pinfunction "GPIO_1_L4") (pintype "passive"))
    )
    (net (code "95") (name "Net-(U1D-GPIO_2)") (class "Default")
      (node (ref "R19") (pin "1") (pinfunction "1_1") (pintype "passive"))
      (node (ref "U1") (pin "J5") (pinfunction "GPIO_2_J5") (pintype "passive"))
    )
    (net (code "96") (name "Net-(U1D-GPIO_3)") (class "Default")
      (node (ref "R20") (pin "1") (pinfunction "1_1") (pintype "passive"))
      (node (ref "U1") (pin "K5") (pinfunction "GPIO_3_K5") (pintype "passive"))
    )
    (net (code "97") (name "Net-(U1D-GPIO_4)") (class "Default")
      (node (ref "R21") (pin "1") (pinfunction "1_1") (pintype "passive"))
      (node (ref "U1") (pin "L5") (pinfunction "GPIO_4_L5") (pintype "passive"))
    )
    (net (code "98") (name "Net-(U1D-GPIO_5)") (class "Default")
      (node (ref "R22") (pin "1") (pinfunction "1_1") (pintype "passive"))
      (node (ref "U1") (pin "K6") (pinfunction "GPIO_5_K6") (pintype "passive"))
    )
    (net (code "99") (name "Net-(U1D-GPIO_6)") (class "Default")
      (node (ref "R23") (pin "1") (pinfunction "1_1") (pintype "passive"))
      (node (ref "U1") (pin "J6") (pinfunction "GPIO_6_J6") (pintype "passive"))
    )
    (net (code "100") (name "Net-(U1D-GPIO_7)") (class "Default")
      (node (ref "R24") (pin "1") (pinfunction "1_1") (pintype "passive"))
      (node (ref "U1") (pin "J7") (pinfunction "GPIO_7_J7") (pintype "passive"))
    )
    (net (code "101") (name "Net-(U1D-GPIO_8)") (class "Default")
      (node (ref "R25") (pin "1") (pinfunction "1_1") (pintype "passive"))
      (node (ref "U1") (pin "L7") (pinfunction "GPIO_8_L7") (pintype "passive"))
    )
    (net (code "102") (name "Net-(U1D-GPIO_9)") (class "Default")
      (node (ref "R26") (pin "1") (pinfunction "1_1") (pintype "passive"))
      (node (ref "U1") (pin "K7") (pinfunction "GPIO_9_K7") (pintype "passive"))
    )
    (net (code "103") (name "Net-(U1D-GPIO_10)") (class "Default")
      (node (ref "R27") (pin "1") (pinfunction "1_1") (pintype "passive"))
      (node (ref "U1") (pin "L6") (pinfunction "GPIO_10_L6") (pintype "passive"))
    )
    (net (code "104") (name "Net-(U1D-GPIO_11)") (class "Default")
      (node (ref "R28") (pin "1") (pinfunction "1_1") (pintype "passive"))
      (node (ref "U1") (pin "L8") (pinfunction "GPIO_11_L8") (pintype "passive"))
    )
    (net (code "105") (name "Net-(U1D-GPIO_12)") (class "Default")
      (node (ref "R29") (pin "1") (pinfunction "1_1") (pintype "passive"))
      (node (ref "U1") (pin "K8") (pinfunction "GPIO_12_K8") (pintype "passive"))
    )
    (net (code "106") (name "Net-(U1D-GPIO_13)") (class "Default")
      (node (ref "R30") (pin "1") (pinfunction "1_1") (pintype "passive"))
      (node (ref "U1") (pin "B10") (pinfunction "GPIO_13_B10") (pintype "passive"))
    )
    (net (code "107") (name "Net-(U1D-GPIO_14)") (class "Default")
      (node (ref "R31") (pin "1") (pinfunction "1_1") (pintype "passive"))
      (node (ref "U1") (pin "B9") (pinfunction "GPIO_14_B9") (pintype "passive"))
    )
    (net (code "108") (name "Net-(U1D-GPIO_15)") (class "Default")
      (node (ref "R32") (pin "1") (pinfunction "1_1") (pintype "passive"))
      (node (ref "U1") (pin "A10") (pinfunction "GPIO_15_A10") (pintype "passive"))
    )
    (net (code "109") (name "Net-(U1D-GPIO_16)") (class "Default")
      (node (ref "R33") (pin "1") (pinfunction "1_1") (pintype "passive"))
      (node (ref "U1") (pin "A9") (pinfunction "GPIO_16_A9") (pintype "passive"))
    )
    (net (code "110") (name "Net-(U1D-GPIO_17)") (class "Default")
      (node (ref "R34") (pin "1") (pinfunction "1_1") (pintype "passive"))
      (node (ref "U1") (pin "B8") (pinfunction "GPIO_17_B8") (pintype "passive"))
    )
    (net (code "111") (name "Net-(U1D-GPIO_18)") (class "Default")
      (node (ref "R35") (pin "1") (pinfunction "1_1") (pintype "passive"))
      (node (ref "U1") (pin "A8") (pinfunction "GPIO_18_A8") (pintype "passive"))
    )
    (net (code "112") (name "Net-(U1D-GPIO_19)") (class "Default")
      (node (ref "R36") (pin "1") (pinfunction "1_1") (pintype "passive"))
      (node (ref "U1") (pin "B6") (pinfunction "GPIO_19_B6") (pintype "passive"))
    )
    (net (code "113") (name "Net-(U1D-GPIO_20)") (class "Default")
      (node (ref "R37") (pin "1") (pinfunction "1_1") (pintype "passive"))
      (node (ref "U1") (pin "B7") (pinfunction "GPIO_20_B7") (pintype "passive"))
    )
    (net (code "114") (name "Net-(U1D-GPIO_21)") (class "Default")
      (node (ref "R38") (pin "1") (pinfunction "1_1") (pintype "passive"))
      (node (ref "U1") (pin "A7") (pinfunction "GPIO_21_A7") (pintype "passive"))
    )
    (net (code "115") (name "Net-(U1D-GPIO_22)") (class "Default")
      (node (ref "R39") (pin "1") (pinfunction "1_1") (pintype "passive"))
      (node (ref "U1") (pin "C7") (pinfunction "GPIO_22_C7") (pintype "passive"))
    )
    (net (code "116") (name "Net-(U1D-GPIO_23)") (class "Default")
      (node (ref "R40") (pin "1") (pinfunction "1_1") (pintype "passive"))
      (node (ref "U1") (pin "C6") (pinfunction "GPIO_23_C6") (pintype "passive"))
    )
    (net (code "117") (name "Net-(U2A-PC_CLK)") (class "Default")
      (node (ref "R81") (pin "2") (pinfunction "2_2") (pintype "passive"))
      (node (ref "U2") (pin "F9") (pinfunction "PC_CLK_F9") (pintype "passive"))
    )
    (net (code "118") (name "Net-(U2A-PC_RDDATA_OUT)") (class "Default")
      (node (ref "R83") (pin "2") (pinfunction "2_2") (pintype "passive"))
      (node (ref "U2") (pin "G10") (pinfunction "PC_RDDATA_OUT_G10") (pintype "passive"))
    )
    (net (code "119") (name "Net-(U2A-PC_RDRDY_OUT)") (class "Default")
      (node (ref "R82") (pin "2") (pinfunction "2_2") (pintype "passive"))
      (node (ref "U2") (pin "F10") (pinfunction "PC_RDRDY_OUT_F10") (pintype "passive"))
    )
    (net (code "120") (name "Net-(U2A-PC_RDREQ)") (class "Default")
      (node (ref "R84") (pin "2") (pinfunction "2_2") (pintype "passive"))
      (node (ref "U2") (pin "J7") (pinfunction "PC_RDREQ_J7") (pintype "passive"))
    )
    (net (code "121") (name "Net-(U2A-PC_RESETN)") (class "Default")
      (node (ref "R85") (pin "2") (pinfunction "2_2") (pintype "passive"))
      (node (ref "U2") (pin "K7") (pinfunction "PC_RESETN_K7") (pintype "passive"))
    )
    (net (code "122") (name "Net-(U2A-PC_WRDATA)") (class "Default")
      (node (ref "R80") (pin "2") (pinfunction "2_2") (pintype "passive"))
      (node (ref "U2") (pin "E10") (pinfunction "PC_WRDATA_E10") (pintype "passive"))
    )
    (net (code "123") (name "Net-(U2A-PC_WRREQ)") (class "Default")
      (node (ref "R79") (pin "2") (pinfunction "2_2") (pintype "passive"))
      (node (ref "U2") (pin "E9") (pinfunction "PC_WRREQ_E9") (pintype "passive"))
    )
    (net (code "124") (name "Net-(U2C-VDD_ABUF)") (class "Default")
      (node (ref "C59") (pin "2") (pinfunction "2_2") (pintype "passive"))
      (node (ref "P5") (pin "3") (pinfunction "3_3") (pintype "passive"))
      (node (ref "U2") (pin "D9") (pinfunction "VDD_ABUF_D9") (pintype "passive"))
    )
    (net (code "125") (name "Net-(U2D-M3_VDD_0P6)") (class "Default")
      (node (ref "P4") (pin "3") (pinfunction "3_3") (pintype "passive"))
      (node (ref "U2") (pin "D2") (pinfunction "M3_VDD_0P6_D2") (pintype "passive"))
    )
    (net (code "126") (name "Net-(U2D-M3_VDD_1P2)") (class "Default")
      (node (ref "P4") (pin "1") (pinfunction "1_1") (pintype "passive"))
      (node (ref "U2") (pin "D1") (pinfunction "M3_VDD_1P2_D1") (pintype "passive"))
    )
    (net (code "127") (name "VCC_0P6") (class "Default")
      (node (ref "P2") (pin "3") (pinfunction "3_3") (pintype "passive"))
    )
    (net (code "128") (name "VCC_1P2") (class "Default")
      (node (ref "P2") (pin "5") (pinfunction "5_5") (pintype "passive"))
      (node (ref "P5") (pin "6") (pinfunction "6_6") (pintype "passive"))
    )
    (net (code "129") (name "VCC_BAT") (class "Default")
      (node (ref "P2") (pin "7") (pinfunction "7_7") (pintype "passive"))
      (node (ref "P5") (pin "2") (pinfunction "2_2") (pintype "passive"))
      (node (ref "P5") (pin "4") (pinfunction "4_4") (pintype "passive"))
    )
    (net (code "130") (name "VCC_SOL") (class "Default")
      (node (ref "P2") (pin "1") (pinfunction "1_1") (pintype "passive"))
    )
  )
)
